# RS232.net
KiCad netlist of a schematic drawn in Altium Designer
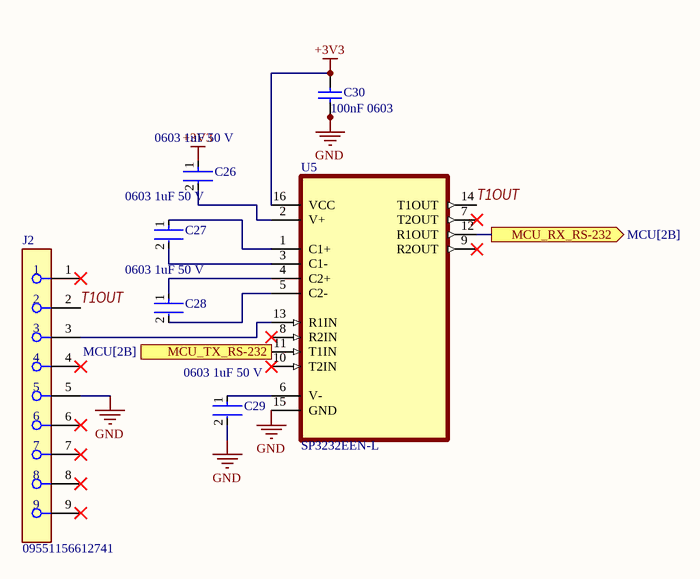
[diagram p0: RS232.SchDoc]

(export (version "E")
  (design (tool "Eeschema 10.0.6"))
  (components
    (comp (ref "C26")
      (value "0603 1uF 50 V")
      (footprint "FP-CC0603-DB-MFG")
      (description "CAP CER 1UF 50V X7R 0603")
      (fields (field (name "TOLERANCE") "10%"))
      (libsource (lib "Altium Content Vault") (part "11868f565c42a9108669ba33697ecf6"))
    )
    (comp (ref "C27")
      (value "0603 1uF 50 V")
      (footprint "FP-CC0603-DB-MFG")
      (description "CAP CER 1UF 50V X7R 0603")
      (fields (field (name "TOLERANCE") "10%"))
      (libsource (lib "Altium Content Vault") (part "11868f565c42a9108669ba33697ecf6"))
    )
    (comp (ref "C28")
      (value "0603 1uF 50 V")
      (footprint "FP-CC0603-DB-MFG")
      (description "CAP CER 1UF 50V X7R 0603")
      (fields (field (name "TOLERANCE") "10%"))
      (libsource (lib "Altium Content Vault") (part "11868f565c42a9108669ba33697ecf6"))
    )
    (comp (ref "C29")
      (value "0603 1uF 50 V")
      (footprint "FP-CC0603-DB-MFG")
      (description "CAP CER 1UF 50V X7R 0603")
      (fields (field (name "TOLERANCE") "10%"))
      (libsource (lib "Altium Content Vault") (part "11868f565c42a9108669ba33697ecf6"))
    )
    (comp (ref "C30")
      (value "100nF 0603")
      (footprint "CAPC1608X90X35LL15T15")
      (fields
        (field (name "MANUFACTURER") "AVX Interconnect / Elco")
        (field (name "PART NUMBER") "06035C104KAZ2A")
      )
      (libsource (lib "Altium Content Vault") (part "CAP"))
    )
    (comp (ref "J2")
      (value "09551156612741")
      (footprint "FP-09551156612741-MFG")
      (description "CONN D-SUB RCPT 9POS SMD SLDR")
      (libsource (lib "Altium Content Vault") (part "d3bf64047269a9dc9b641cdda8ee9d2"))
    )
    (comp (ref "U5")
      (value "SP3232EEN-L")
      (footprint "SOIC127P600X175-16N")
      (description "2/2 Transceiver Full RS232 16-SOIC")
      (fields (field (name "MF") "MaxLinear, Inc."))
      (libsource (lib "SP3232EEN-L") (part "SP3232EEN-L"))
    )
  )
  (nets
    (net (code "1") (name "+3V3") (class "Default")
      (node (ref "C26") (pin "1") (pinfunction "1_1") (pintype "passive"))
      (node (ref "C30") (pin "2") (pinfunction "2_2") (pintype "passive"))
      (node (ref "U5") (pin "16") (pinfunction "VCC_16") (pintype "power_in"))
    )
    (net (code "2") (name "/MCU_RX_RS-232") (class "Default")
      (node (ref "U5") (pin "12") (pinfunction "R1OUT_12") (pintype "output"))
    )
    (net (code "3") (name "/MCU_TX_RS-232") (class "Default")
      (node (ref "U5") (pin "11") (pinfunction "T1IN_11") (pintype "input"))
    )
    (net (code "4") (name "/T1OUT") (class "Default")
      (node (ref "J2") (pin "2") (pinfunction "2_2") (pintype "passive"))
      (node (ref "U5") (pin "14") (pinfunction "T1OUT_14") (pintype "output"))
    )
    (net (code "5") (name "GND") (class "Default")
      (node (ref "C29") (pin "2") (pinfunction "2_2") (pintype "passive"))
      (node (ref "C30") (pin "1") (pinfunction "1_1") (pintype "passive"))
      (node (ref "J2") (pin "5") (pinfunction "5_5") (pintype "passive"))
      (node (ref "U5") (pin "15") (pinfunction "GND_15") (pintype "passive"))
    )
    (net (code "6") (name "Net-(U5-C1+)") (class "Default")
      (node (ref "C27") (pin "1") (pinfunction "1_1") (pintype "passive"))
      (node (ref "U5") (pin "1") (pinfunction "C1+_1") (pintype "passive"))
    )
    (net (code "7") (name "Net-(U5-C1-)") (class "Default")
      (node (ref "C27") (pin "2") (pinfunction "2_2") (pintype "passive"))
      (node (ref "U5") (pin "3") (pinfunction "C1-_3") (pintype "passive"))
    )
    (net (code "8") (name "Net-(U5-C2+)") (class "Default")
      (node (ref "C28") (pin "1") (pinfunction "1_1") (pintype "passive"))
      (node (ref "U5") (pin "4") (pinfunction "C2+_4") (pintype "passive"))
    )
    (net (code "9") (name "Net-(U5-C2-)") (class "Default")
      (node (ref "C28") (pin "2") (pinfunction "2_2") (pintype "passive"))
      (node (ref "U5") (pin "5") (pinfunction "C2-_5") (pintype "passive"))
    )
    (net (code "10") (name "Net-(U5-R1IN)") (class "Default")
      (node (ref "J2") (pin "3") (pinfunction "3_3") (pintype "passive"))
      (node (ref "U5") (pin "13") (pinfunction "R1IN_13") (pintype "input"))
    )
    (net (code "11") (name "Net-(U5-V+)") (class "Default")
      (node (ref "C26") (pin "2") (pinfunction "2_2") (pintype "passive"))
      (node (ref "U5") (pin "2") (pinfunction "V+_2") (pintype "power_in"))
    )
    (net (code "12") (name "Net-(U5-V-)") (class "Default")
      (node (ref "C29") (pin "1") (pinfunction "1_1") (pintype "passive"))
      (node (ref "U5") (pin "6") (pinfunction "V-_6") (pintype "power_in"))
    )
    (net (code "13") (name "unconnected-(J2-Pad1)") (class "Default")
      (node (ref "J2") (pin "1") (pinfunction "1_1") (pintype "passive+no_connect"))
    )
    (net (code "14") (name "unconnected-(J2-Pad4)") (class "Default")
      (node (ref "J2") (pin "4") (pinfunction "4_4") (pintype "passive+no_connect"))
    )
    (net (code "15") (name "unconnected-(J2-Pad6)") (class "Default")
      (node (ref "J2") (pin "6") (pinfunction "6_6") (pintype "passive+no_connect"))
    )
    (net (code "16") (name "unconnected-(J2-Pad7)") (class "Default")
      (node (ref "J2") (pin "7") (pinfunction "7_7") (pintype "passive+no_connect"))
    )
    (net (code "17") (name "unconnected-(J2-Pad8)") (class "Default")
      (node (ref "J2") (pin "8") (pinfunction "8_8") (pintype "passive+no_connect"))
    )
    (net (code "18") (name "unconnected-(J2-Pad9)") (class "Default")
      (node (ref "J2") (pin "9") (pinfunction "9_9") (pintype "passive+no_connect"))
    )
    (net (code "19") (name "unconnected-(U5-R2IN-Pad8)") (class "Default")
      (node (ref "U5") (pin "8") (pinfunction "R2IN_8") (pintype "input+no_connect"))
    )
    (net (code "20") (name "unconnected-(U5-R2OUT-Pad9)") (class "Default")
      (node (ref "U5") (pin "9") (pinfunction "R2OUT_9") (pintype "output+no_connect"))
    )
    (net (code "21") (name "unconnected-(U5-T2IN-Pad10)") (class "Default")
      (node (ref "U5") (pin "10") (pinfunction "T2IN_10") (pintype "input+no_connect"))
    )
    (net (code "22") (name "unconnected-(U5-T2OUT-Pad7)") (class "Default")
      (node (ref "U5") (pin "7") (pinfunction "T2OUT_7") (pintype "output+no_connect"))
    )
  )
)
